# EtherTen.net
KiCad netlist of a schematic drawn in EAGLE
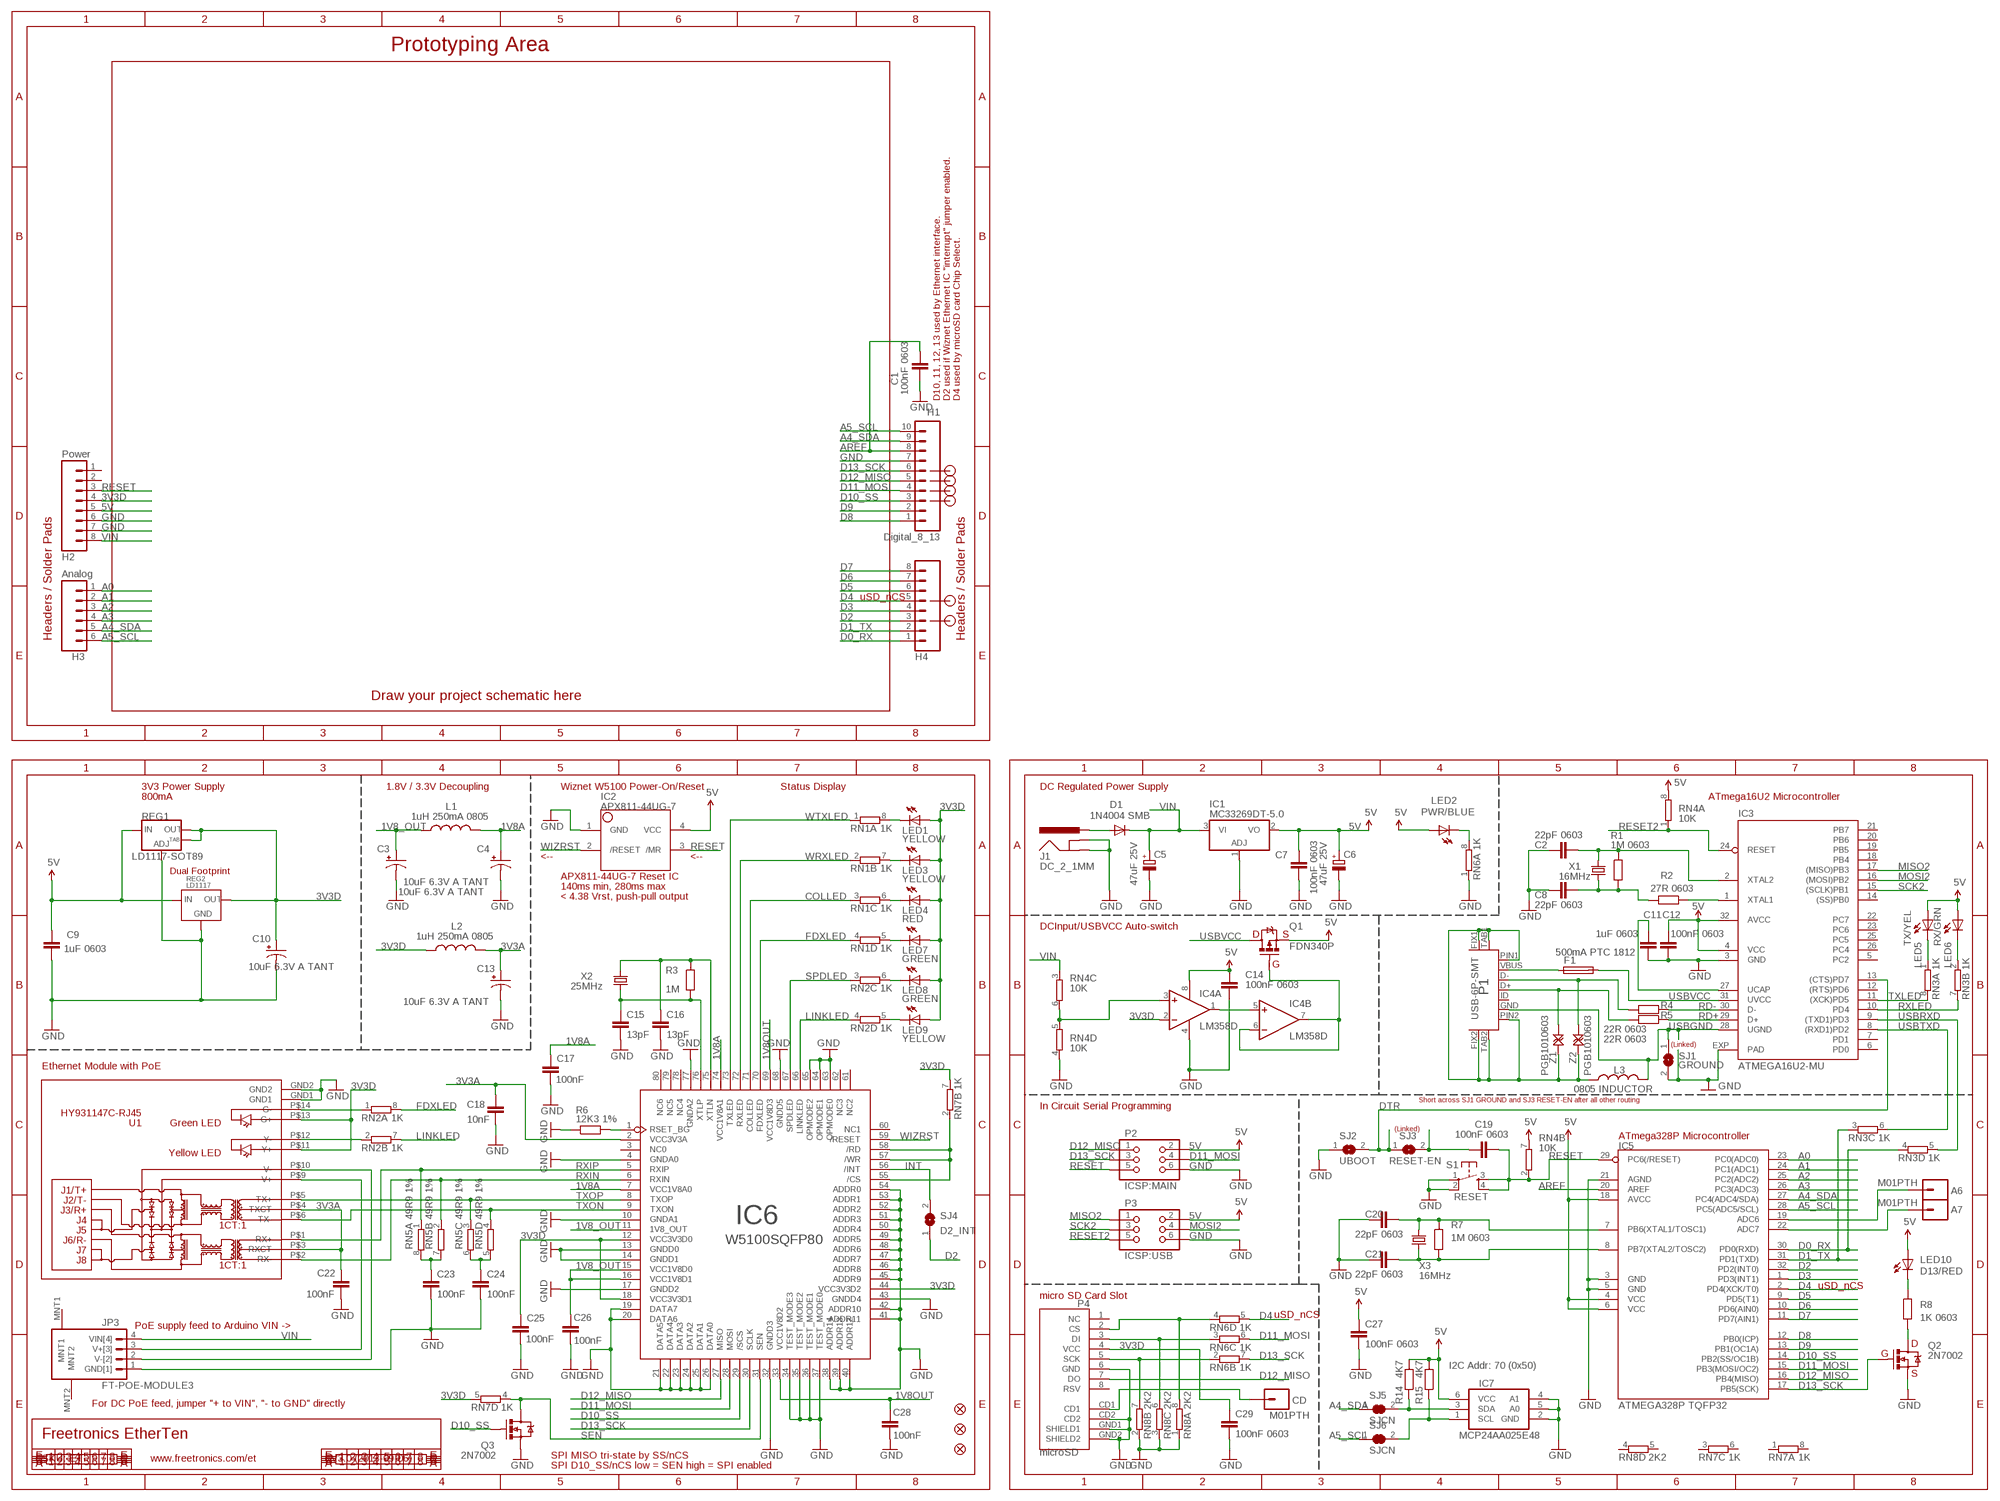
[diagram p0: schematic, sheet 1]

(export (version "E")
  (design (tool "Eeschema 10.0.6"))
  (components
    (comp (ref "A6")
      (value "M01PTH")
      (footprint "eagle-import:1X01")
      (libsource (lib "eagle-import") (part "M01PTH"))
    )
    (comp (ref "A7")
      (value "M01PTH")
      (footprint "eagle-import:1X01")
      (libsource (lib "eagle-import") (part "M01PTH"))
    )
    (comp (ref "C1")
      (value "100nF 0603")
      (footprint "eagle-import:C0603")
      (libsource (lib "eagle-import") (part "CAP0603"))
    )
    (comp (ref "C2")
      (value "22pF 0603")
      (footprint "eagle-import:C0603")
      (libsource (lib "eagle-import") (part "CAP0603"))
    )
    (comp (ref "C3")
      (value "10uF 6.3V A TANT")
      (footprint "eagle-import:EIA3216")
      (libsource (lib "eagle-import") (part "CAP_POL1206"))
    )
    (comp (ref "C4")
      (value "10uF 6.3V A TANT")
      (footprint "eagle-import:EIA3216")
      (libsource (lib "eagle-import") (part "CAP_POL1206"))
    )
    (comp (ref "C5")
      (value "47uF 25V")
      (footprint "eagle-import:PANASONIC_D")
      (libsource (lib "eagle-import") (part "CPOL-EUD"))
    )
    (comp (ref "C6")
      (value "47uF 25V")
      (footprint "eagle-import:PANASONIC_D")
      (libsource (lib "eagle-import") (part "CPOL-EUD"))
    )
    (comp (ref "C7")
      (value "100nF 0603")
      (footprint "eagle-import:C0603")
      (libsource (lib "eagle-import") (part "CAP0603"))
    )
    (comp (ref "C8")
      (value "22pF 0603")
      (footprint "eagle-import:C0603")
      (libsource (lib "eagle-import") (part "CAP0603"))
    )
    (comp (ref "C9")
      (value "1uF 0603")
      (footprint "eagle-import:C0603")
      (libsource (lib "eagle-import") (part "CAP0603"))
    )
    (comp (ref "C10")
      (value "10uF 6.3V A TANT")
      (footprint "eagle-import:EIA3216")
      (libsource (lib "eagle-import") (part "CAP_POL1206"))
    )
    (comp (ref "C11")
      (value "1uF 0603")
      (footprint "eagle-import:C0603")
      (libsource (lib "eagle-import") (part "CAP0603"))
    )
    (comp (ref "C12")
      (value "100nF 0603")
      (footprint "eagle-import:C0603")
      (libsource (lib "eagle-import") (part "CAP0603"))
    )
    (comp (ref "C13")
      (value "10uF 6.3V A TANT")
      (footprint "eagle-import:EIA3216")
      (libsource (lib "eagle-import") (part "CAP_POL1206"))
    )
    (comp (ref "C14")
      (value "100nF 0603")
      (footprint "eagle-import:C0603")
      (libsource (lib "eagle-import") (part "CAP0603"))
    )
    (comp (ref "C15")
      (value "13pF")
      (footprint "eagle-import:C0603")
      (libsource (lib "eagle-import") (part "CAP0603"))
    )
    (comp (ref "C16")
      (value "13pF")
      (footprint "eagle-import:C0603")
      (libsource (lib "eagle-import") (part "CAP0603"))
    )
    (comp (ref "C17")
      (value "100nF")
      (footprint "eagle-import:C0603")
      (libsource (lib "eagle-import") (part "CAP0603"))
    )
    (comp (ref "C18")
      (value "10nF")
      (footprint "eagle-import:C0603")
      (libsource (lib "eagle-import") (part "CAP0603"))
    )
    (comp (ref "C19")
      (value "100nF 0603")
      (footprint "eagle-import:C0603")
      (libsource (lib "eagle-import") (part "CAP0603"))
    )
    (comp (ref "C20")
      (value "22pF 0603")
      (footprint "eagle-import:C0603")
      (libsource (lib "eagle-import") (part "CAP0603"))
    )
    (comp (ref "C21")
      (value "22pF 0603")
      (footprint "eagle-import:C0603")
      (libsource (lib "eagle-import") (part "CAP0603"))
    )
    (comp (ref "C22")
      (value "100nF")
      (footprint "eagle-import:C0603")
      (libsource (lib "eagle-import") (part "CAP0603"))
    )
    (comp (ref "C23")
      (value "100nF")
      (footprint "eagle-import:C0603")
      (libsource (lib "eagle-import") (part "CAP0603"))
    )
    (comp (ref "C24")
      (value "100nF")
      (footprint "eagle-import:C0603")
      (libsource (lib "eagle-import") (part "CAP0603"))
    )
    (comp (ref "C25")
      (value "100nF")
      (footprint "eagle-import:C0603")
      (libsource (lib "eagle-import") (part "CAP0603"))
    )
    (comp (ref "C26")
      (value "100nF")
      (footprint "eagle-import:C0603")
      (libsource (lib "eagle-import") (part "CAP0603"))
    )
    (comp (ref "C27")
      (value "100nF 0603")
      (footprint "eagle-import:C0603")
      (libsource (lib "eagle-import") (part "CAP0603"))
    )
    (comp (ref "C28")
      (value "100nF")
      (footprint "eagle-import:C0603")
      (libsource (lib "eagle-import") (part "CAP0603"))
    )
    (comp (ref "C29")
      (value "100nF 0603")
      (footprint "eagle-import:C0603")
      (libsource (lib "eagle-import") (part "CAP0603"))
    )
    (comp (ref "CD")
      (value "M01PTH")
      (footprint "eagle-import:1X01")
      (libsource (lib "eagle-import") (part "M01PTH"))
    )
    (comp (ref "D1")
      (value "1N4004 SMB")
      (footprint "eagle-import:SMA-DIODE")
      (libsource (lib "eagle-import") (part "DIODESMA"))
    )
    (comp (ref "F1")
      (value "500mA PTC 1812")
      (footprint "eagle-import:1812")
      (libsource (lib "eagle-import") (part "PTC050"))
    )
    (comp (ref "FID1")
      (value "FIDUCIAL1X2.5")
      (footprint "eagle-import:FIDUCIAL-1X2.5")
      (libsource (lib "eagle-import") (part "FIDUCIAL1X2.5"))
    )
    (comp (ref "FID2")
      (value "FIDUCIAL1X2.5")
      (footprint "eagle-import:FIDUCIAL-1X2.5")
      (libsource (lib "eagle-import") (part "FIDUCIAL1X2.5"))
    )
    (comp (ref "FID3")
      (value "FIDUCIAL1X2.5")
      (footprint "eagle-import:FIDUCIAL-1X2.5")
      (libsource (lib "eagle-import") (part "FIDUCIAL1X2.5"))
    )
    (comp (ref "H1")
      (value "Digital_8_13")
      (footprint "eagle-import:1X10-S")
      (libsource (lib "eagle-import") (part "M10-SOCKET"))
    )
    (comp (ref "H2")
      (value "Power")
      (footprint "eagle-import:1X08-S")
      (libsource (lib "eagle-import") (part "M08-SOCKET"))
    )
    (comp (ref "H3")
      (value "Analog")
      (footprint "eagle-import:1X06-S")
      (libsource (lib "eagle-import") (part "M06-SOCKET"))
    )
    (comp (ref "H4")
      (value "Digital_0_7")
      (footprint "eagle-import:1X08-S")
      (libsource (lib "eagle-import") (part "M08-SOCKET"))
    )
    (comp (ref "IC1")
      (value "MC33269DT-5.0")
      (footprint "eagle-import:DPACK")
      (libsource (lib "eagle-import") (part "MC33269?D-5.0"))
    )
    (comp (ref "IC2")
      (value "APX811-44UG-7")
      (footprint "eagle-import:SOT143-R")
      (libsource (lib "eagle-import") (part "APX81X"))
    )
    (comp (ref "IC3")
      (value "ATMEGA16U2-MU")
      (footprint "eagle-import:ATMEL_QFN32")
      (libsource (lib "eagle-import") (part "ATMEGA8U2QFN"))
    )
    (comp (ref "IC4")
      (value "LM358D")
      (footprint "eagle-import:SO08")
      (libsource (lib "eagle-import") (part "LM358D"))
    )
    (comp (ref "IC5")
      (value "ATMEGA328P TQFP32")
      (footprint "eagle-import:TQFP32-08")
      (libsource (lib "eagle-import") (part "AVR-MEGA8-AI"))
    )
    (comp (ref "IC6")
      (value "W5100SQFP80")
      (footprint "eagle-import:SQFP80")
      (libsource (lib "eagle-import") (part "W5100SQFP80"))
    )
    (comp (ref "IC7")
      (value "MCP24AA025E48")
      (footprint "eagle-import:SOT23-6")
      (libsource (lib "eagle-import") (part "MCP24AA025E48"))
    )
    (comp (ref "J1")
      (value "DC_2_1MM")
      (footprint "eagle-import:POWER_JACK_SLOTS")
      (libsource (lib "eagle-import") (part "POWER_JACK-SLOTS"))
    )
    (comp (ref "JP3")
      (value "FT-POE-MODULE3")
      (footprint "eagle-import:FT-POE-MODULE-NOLABEL")
      (libsource (lib "eagle-import") (part "FT-POE-MODULE3"))
    )
    (comp (ref "L1")
      (value "1uH 250mA 0805")
      (footprint "eagle-import:L2012C")
      (libsource (lib "eagle-import") (part "L-USL2012C"))
    )
    (comp (ref "L2")
      (value "1uH 250mA 0805")
      (footprint "eagle-import:L2012C")
      (libsource (lib "eagle-import") (part "L-USL2012C"))
    )
    (comp (ref "L3")
      (value "0805 INDUCTOR")
      (footprint "eagle-import:0805-LARGE")
      (libsource (lib "eagle-import") (part "INDUCTOR0805-LARGE"))
    )
    (comp (ref "LED1")
      (value "YELLOW")
      (footprint "eagle-import:LED-0603")
      (libsource (lib "eagle-import") (part "LED0603"))
    )
    (comp (ref "LED2")
      (value "PWR/BLUE")
      (footprint "eagle-import:LED-0603")
      (libsource (lib "eagle-import") (part "LED0603"))
    )
    (comp (ref "LED3")
      (value "YELLOW")
      (footprint "eagle-import:LED-0603")
      (libsource (lib "eagle-import") (part "LED0603"))
    )
    (comp (ref "LED4")
      (value "RED")
      (footprint "eagle-import:LED-0603")
      (libsource (lib "eagle-import") (part "LED0603"))
    )
    (comp (ref "LED5")
      (value "TX/YEL")
      (footprint "eagle-import:LED-0603")
      (libsource (lib "eagle-import") (part "LED0603"))
    )
    (comp (ref "LED6")
      (value "RX/GRN")
      (footprint "eagle-import:LED-0603")
      (libsource (lib "eagle-import") (part "LED0603"))
    )
    (comp (ref "LED7")
      (value "GREEN")
      (footprint "eagle-import:LED-0603")
      (libsource (lib "eagle-import") (part "LED0603"))
    )
    (comp (ref "LED8")
      (value "GREEN")
      (footprint "eagle-import:LED-0603")
      (libsource (lib "eagle-import") (part "LED0603"))
    )
    (comp (ref "LED9")
      (value "YELLOW")
      (footprint "eagle-import:LED-0603")
      (libsource (lib "eagle-import") (part "LED0603"))
    )
    (comp (ref "LED10")
      (value "D13/RED")
      (footprint "eagle-import:LED-0603")
      (libsource (lib "eagle-import") (part "LED0603"))
    )
    (comp (ref "P1")
      (value "USB-6P-SMT")
      (footprint "eagle-import:USB-MICROB-MB05PMXX")
      (libsource (lib "eagle-import") (part "USB-6P-SMT"))
    )
    (comp (ref "P2")
      (value "ICSP:MAIN")
      (footprint "eagle-import:2X03PTH")
      (libsource (lib "eagle-import") (part "ICSPPTH"))
    )
    (comp (ref "P3")
      (value "ICSP:USB")
      (footprint "eagle-import:2X03PTH")
      (libsource (lib "eagle-import") (part "ICSPPTH"))
    )
    (comp (ref "P4")
      (value "microSD")
      (footprint "eagle-import:MICRO-SD-SOCKET-PP")
      (libsource (lib "eagle-import") (part "USD-SOCKETNEW"))
    )
    (comp (ref "Q1")
      (value "FDN340P")
      (footprint "eagle-import:SOT23")
      (libsource (lib "eagle-import") (part "MOSFET-PCHANNEL"))
    )
    (comp (ref "Q2")
      (value "2N7002")
      (footprint "eagle-import:SOT23-3")
      (libsource (lib "eagle-import") (part "MOSFET-NCHANNEL-233"))
    )
    (comp (ref "Q3")
      (value "2N7002")
      (footprint "eagle-import:SOT23-3")
      (libsource (lib "eagle-import") (part "MOSFET-NCHANNEL-233"))
    )
    (comp (ref "R1")
      (value "1M 0603")
      (footprint "eagle-import:R0603")
      (libsource (lib "eagle-import") (part "RESISTOR0603"))
    )
    (comp (ref "R2")
      (value "27R 0603")
      (footprint "eagle-import:R0603")
      (libsource (lib "eagle-import") (part "RESISTOR0603"))
    )
    (comp (ref "R3")
      (value "1M")
      (footprint "eagle-import:R0603")
      (libsource (lib "eagle-import") (part "RESISTOR0603"))
    )
    (comp (ref "R4")
      (value "22R 0603")
      (footprint "eagle-import:R0603")
      (libsource (lib "eagle-import") (part "RESISTOR0603"))
    )
    (comp (ref "R5")
      (value "22R 0603")
      (footprint "eagle-import:R0603")
      (libsource (lib "eagle-import") (part "RESISTOR0603"))
    )
    (comp (ref "R6")
      (value "12K3 1%")
      (footprint "eagle-import:R0603")
      (libsource (lib "eagle-import") (part "RESISTOR0603"))
    )
    (comp (ref "R7")
      (value "1M 0603")
      (footprint "eagle-import:R0603")
      (libsource (lib "eagle-import") (part "RESISTOR0603"))
    )
    (comp (ref "R8")
      (value "1K 0603")
      (footprint "eagle-import:R0603")
      (libsource (lib "eagle-import") (part "RESISTOR0603"))
    )
    (comp (ref "R14")
      (value "4K7")
      (footprint "eagle-import:R0603")
      (libsource (lib "eagle-import") (part "RESISTOR0603"))
    )
    (comp (ref "R15")
      (value "4K7")
      (footprint "eagle-import:R0603")
      (libsource (lib "eagle-import") (part "RESISTOR0603"))
    )
    (comp (ref "REG1")
      (value "LD1117-SOT89")
      (footprint "eagle-import:SOT89")
      (libsource (lib "eagle-import") (part "V_REG_LM1117SOT89"))
    )
    (comp (ref "REG2")
      (value "LD1117")
      (footprint "eagle-import:SOT-223")
      (libsource (lib "eagle-import") (part "LD1117"))
    )
    (comp (ref "RN1")
      (value "1K")
      (footprint "eagle-import:CAY16")
      (libsource (lib "eagle-import") (part "4R-NCAY16"))
    )
    (comp (ref "RN2")
      (value "1K")
      (footprint "eagle-import:CAY16")
      (libsource (lib "eagle-import") (part "4R-NCAY16"))
    )
    (comp (ref "RN3")
      (value "1K")
      (footprint "eagle-import:CAY16")
      (libsource (lib "eagle-import") (part "4R-NCAY16"))
    )
    (comp (ref "RN4")
      (value "10K")
      (footprint "eagle-import:CAY16")
      (libsource (lib "eagle-import") (part "4R-NCAY16"))
    )
    (comp (ref "RN5")
      (value "49R9 1%")
      (footprint "eagle-import:CAY16")
      (libsource (lib "eagle-import") (part "4R-NCAY16"))
    )
    (comp (ref "RN6")
      (value "1K")
      (footprint "eagle-import:CAY16")
      (libsource (lib "eagle-import") (part "4R-NCAY16"))
    )
    (comp (ref "RN7")
      (value "1K")
      (footprint "eagle-import:CAY16")
      (libsource (lib "eagle-import") (part "4R-NCAY16"))
    )
    (comp (ref "RN8")
      (value "2K2")
      (footprint "eagle-import:CAY16")
      (libsource (lib "eagle-import") (part "4R-NCAY16"))
    )
    (comp (ref "S1")
      (value "RESET")
      (footprint "eagle-import:TACTILE_SMD-6MM")
      (libsource (lib "eagle-import") (part "TAC_SWITCH-SMT-6"))
    )
    (comp (ref "SJ1")
      (value "GROUND")
      (footprint "eagle-import:SJ")
      (libsource (lib "eagle-import") (part "SJ"))
    )
    (comp (ref "SJ2")
      (value "UBOOT")
      (footprint "eagle-import:SJ")
      (libsource (lib "eagle-import") (part "SJ"))
    )
    (comp (ref "SJ3")
      (value "RESET-EN")
      (footprint "eagle-import:SJ")
      (libsource (lib "eagle-import") (part "SJ"))
    )
    (comp (ref "SJ4")
      (value "D2_INT")
      (footprint "eagle-import:SJ")
      (libsource (lib "eagle-import") (part "SJ"))
    )
    (comp (ref "SJ5")
      (value "SJCN")
      (footprint "eagle-import:SJC")
      (libsource (lib "eagle-import") (part "SJCN"))
    )
    (comp (ref "SJ6")
      (value "SJCN")
      (footprint "eagle-import:SJC")
      (libsource (lib "eagle-import") (part "SJCN"))
    )
    (comp (ref "U1")
      (value "HY931147C-RJ45")
      (footprint "eagle-import:HY931147C")
      (libsource (lib "eagle-import") (part "HY931147C-RJ45"))
    )
    (comp (ref "X1")
      (value "16MHz")
      (footprint "eagle-import:HC49U-V")
      (libsource (lib "eagle-import") (part "CRYSTALHC49UV"))
    )
    (comp (ref "X2")
      (value "25MHz")
      (footprint "eagle-import:HC49U-V")
      (libsource (lib "eagle-import") (part "CRYSTALHC49UV"))
    )
    (comp (ref "X3")
      (value "16MHz")
      (footprint "eagle-import:HC49U-V")
      (libsource (lib "eagle-import") (part "CRYSTALHC49UV"))
    )
    (comp (ref "Z1")
      (value "PGB1010603")
      (footprint "eagle-import:TVS0603")
      (libsource (lib "eagle-import") (part "TVS0603"))
    )
    (comp (ref "Z2")
      (value "PGB1010603")
      (footprint "eagle-import:TVS0603")
      (libsource (lib "eagle-import") (part "TVS0603"))
    )
  )
  (nets
    (net (code "1") (name "/1V8A") (class "Default")
      (node (ref "C17") (pin "1") (pinfunction "1_1") (pintype "passive"))
      (node (ref "C4") (pin "A") (pinfunction "+_A") (pintype "passive"))
      (node (ref "IC6") (pin "7") (pinfunction "VCC1V8A0_7") (pintype "bidirectional"))
      (node (ref "IC6") (pin "74") (pinfunction "VCC1V8A1_74") (pintype "bidirectional"))
      (node (ref "L1") (pin "2") (pinfunction "2_2") (pintype "passive"))
    )
    (net (code "2") (name "/1V8OUT") (class "Default")
      (node (ref "C28") (pin "1") (pinfunction "1_1") (pintype "passive"))
      (node (ref "IC6") (pin "33") (pinfunction "VCC1V8D2_33") (pintype "bidirectional"))
      (node (ref "IC6") (pin "69") (pinfunction "VCC1V8D3_69") (pintype "bidirectional"))
    )
    (net (code "3") (name "/1V8_OUT") (class "Default")
      (node (ref "C26") (pin "1") (pinfunction "1_1") (pintype "passive"))
      (node (ref "C3") (pin "A") (pinfunction "+_A") (pintype "passive"))
      (node (ref "IC6") (pin "11") (pinfunction "1V8_OUT_11") (pintype "bidirectional"))
      (node (ref "IC6") (pin "15") (pinfunction "VCC1V8D0_15") (pintype "bidirectional"))
      (node (ref "IC6") (pin "16") (pinfunction "VCC1V8D1_16") (pintype "bidirectional"))
      (node (ref "L1") (pin "1") (pinfunction "1_1") (pintype "passive"))
    )
    (net (code "4") (name "/3V3A") (class "Default")
      (node (ref "C13") (pin "A") (pinfunction "+_A") (pintype "passive"))
      (node (ref "C18") (pin "1") (pinfunction "1_1") (pintype "passive"))
      (node (ref "C22") (pin "1") (pinfunction "1_1") (pintype "passive"))
      (node (ref "IC6") (pin "2") (pinfunction "VCC3V3A_2") (pintype "bidirectional"))
      (node (ref "L2") (pin "2") (pinfunction "2_2") (pintype "passive"))
      (node (ref "U1") (pin "P$3") (pinfunction "RXCT_P$3") (pintype "bidirectional"))
      (node (ref "U1") (pin "P$4") (pinfunction "TXCT_P$4") (pintype "bidirectional"))
    )
    (net (code "5") (name "/3V3D") (class "Default")
      (node (ref "C10") (pin "A") (pinfunction "+_A") (pintype "passive"))
      (node (ref "C25") (pin "1") (pinfunction "1_1") (pintype "passive"))
      (node (ref "C29") (pin "1") (pinfunction "1_1") (pintype "passive"))
      (node (ref "H2") (pin "4") (pinfunction "4_4") (pintype "passive"))
      (node (ref "IC4") (pin "2") (pinfunction "-IN_2") (pintype "input"))
      (node (ref "IC6") (pin "12") (pinfunction "VCC3V3D0_12") (pintype "bidirectional"))
      (node (ref "IC6") (pin "18") (pinfunction "VCC3V3D1_18") (pintype "bidirectional"))
      (node (ref "IC6") (pin "44") (pinfunction "VCC3V3D2_44") (pintype "bidirectional"))
      (node (ref "L2") (pin "1") (pinfunction "1_1") (pintype "passive"))
      (node (ref "LED1") (pin "A") (pinfunction "A_A") (pintype "passive"))
      (node (ref "LED3") (pin "A") (pinfunction "A_A") (pintype "passive"))
      (node (ref "LED4") (pin "A") (pinfunction "A_A") (pintype "passive"))
      (node (ref "LED7") (pin "A") (pinfunction "A_A") (pintype "passive"))
      (node (ref "LED8") (pin "A") (pinfunction "A_A") (pintype "passive"))
      (node (ref "LED9") (pin "A") (pinfunction "A_A") (pintype "passive"))
      (node (ref "P4") (pin "4") (pinfunction "VCC_4") (pintype "bidirectional"))
      (node (ref "REG1") (pin "2") (pinfunction "OUT_2") (pintype "output"))
      (node (ref "REG1") (pin "4") (pinfunction "OUT_4") (pintype "output"))
      (node (ref "REG2") (pin "2") (pinfunction "OUT_2") (pintype "power_in"))
      (node (ref "REG2") (pin "4") (pinfunction "OUT_4") (pintype "power_in"))
      (node (ref "RN7") (pin "5") (pinfunction "2_5") (pintype "passive"))
      (node (ref "RN7") (pin "7") (pinfunction "2_7") (pintype "passive"))
      (node (ref "U1") (pin "P$11") (pinfunction "Y+_P$11") (pintype "bidirectional"))
      (node (ref "U1") (pin "P$13") (pinfunction "G+_P$13") (pintype "bidirectional"))
    )
    (net (code "6") (name "/A0") (class "Default")
      (node (ref "H3") (pin "1") (pinfunction "1_1") (pintype "passive"))
      (node (ref "IC5") (pin "23") (pinfunction "PC0(ADC0)_23") (pintype "bidirectional"))
    )
    (net (code "7") (name "/A1") (class "Default")
      (node (ref "H3") (pin "2") (pinfunction "2_2") (pintype "passive"))
      (node (ref "IC5") (pin "24") (pinfunction "PC1(ADC1)_24") (pintype "bidirectional"))
    )
    (net (code "8") (name "/A2") (class "Default")
      (node (ref "H3") (pin "3") (pinfunction "3_3") (pintype "passive"))
      (node (ref "IC5") (pin "25") (pinfunction "PC2(ADC2)_25") (pintype "bidirectional"))
    )
    (net (code "9") (name "/A3") (class "Default")
      (node (ref "H3") (pin "4") (pinfunction "4_4") (pintype "passive"))
      (node (ref "IC5") (pin "26") (pinfunction "PC3(ADC3)_26") (pintype "bidirectional"))
    )
    (net (code "10") (name "/A4_SDA") (class "Default")
      (node (ref "H1") (pin "9") (pinfunction "9_9") (pintype "passive"))
      (node (ref "H3") (pin "5") (pinfunction "5_5") (pintype "passive"))
      (node (ref "IC5") (pin "27") (pinfunction "PC4(ADC4/SDA)_27") (pintype "bidirectional"))
      (node (ref "SJ5") (pin "1") (pinfunction "1_1") (pintype "passive"))
    )
    (net (code "11") (name "/A5_SCL") (class "Default")
      (node (ref "H1") (pin "10") (pinfunction "10_10") (pintype "passive"))
      (node (ref "H3") (pin "6") (pinfunction "6_6") (pintype "passive"))
      (node (ref "IC5") (pin "28") (pinfunction "PC5(ADC5/SCL)_28") (pintype "bidirectional"))
      (node (ref "SJ6") (pin "1") (pinfunction "1_1") (pintype "passive"))
    )
    (net (code "12") (name "/AREF") (class "Default")
      (node (ref "C1") (pin "1") (pinfunction "1_1") (pintype "passive"))
      (node (ref "H1") (pin "8") (pinfunction "8_8") (pintype "passive"))
      (node (ref "IC5") (pin "20") (pinfunction "AREF_20") (pintype "bidirectional"))
    )
    (net (code "13") (name "/COLLED") (class "Default")
      (node (ref "IC6") (pin "71") (pinfunction "COLLED_71") (pintype "bidirectional"))
      (node (ref "RN1") (pin "3") (pinfunction "1_3") (pintype "passive"))
    )
    (net (code "14") (name "/D0_RX") (class "Default")
      (node (ref "H4") (pin "1") (pinfunction "1_1") (pintype "passive"))
      (node (ref "IC5") (pin "30") (pinfunction "PD0(RXD)_30") (pintype "bidirectional"))
      (node (ref "RN3") (pin "4") (pinfunction "1_4") (pintype "passive"))
    )
    (net (code "15") (name "/D1_TX") (class "Default")
      (node (ref "H4") (pin "2") (pinfunction "2_2") (pintype "passive"))
      (node (ref "IC5") (pin "31") (pinfunction "PD1(TXD)_31") (pintype "bidirectional"))
      (node (ref "RN3") (pin "3") (pinfunction "1_3") (pintype "passive"))
    )
    (net (code "16") (name "/D2") (class "Default")
      (node (ref "H4") (pin "3") (pinfunction "3_3") (pintype "passive"))
      (node (ref "IC5") (pin "32") (pinfunction "PD2(INT0)_32") (pintype "bidirectional"))
      (node (ref "SJ4") (pin "1") (pinfunction "1_1") (pintype "passive"))
    )
    (net (code "17") (name "/D3") (class "Default")
      (node (ref "H4") (pin "4") (pinfunction "4_4") (pintype "passive"))
      (node (ref "IC5") (pin "1") (pinfunction "PD3(INT1)_1") (pintype "bidirectional"))
    )
    (net (code "18") (name "/D4") (class "Default")
      (node (ref "H4") (pin "5") (pinfunction "5_5") (pintype "passive"))
      (node (ref "IC5") (pin "2") (pinfunction "PD4(XCK/T0)_2") (pintype "bidirectional"))
      (node (ref "RN6") (pin "5") (pinfunction "2_5") (pintype "passive"))
    )
    (net (code "19") (name "/D5") (class "Default")
      (node (ref "H4") (pin "6") (pinfunction "6_6") (pintype "passive"))
      (node (ref "IC5") (pin "9") (pinfunction "PD5(T1)_9") (pintype "bidirectional"))
    )
    (net (code "20") (name "/D6") (class "Default")
      (node (ref "H4") (pin "7") (pinfunction "7_7") (pintype "passive"))
      (node (ref "IC5") (pin "10") (pinfunction "PD6(AIN0)_10") (pintype "bidirectional"))
    )
    (net (code "21") (name "/D7") (class "Default")
      (node (ref "H4") (pin "8") (pinfunction "8_8") (pintype "passive"))
      (node (ref "IC5") (pin "11") (pinfunction "PD7(AIN1)_11") (pintype "bidirectional"))
    )
    (net (code "22") (name "/D8") (class "Default")
      (node (ref "H1") (pin "1") (pinfunction "1_1") (pintype "passive"))
      (node (ref "IC5") (pin "12") (pinfunction "PB0(ICP)_12") (pintype "bidirectional"))
    )
    (net (code "23") (name "/D9") (class "Default")
      (node (ref "H1") (pin "2") (pinfunction "2_2") (pintype "passive"))
      (node (ref "IC5") (pin "13") (pinfunction "PB1(OC1A)_13") (pintype "bidirectional"))
    )
    (net (code "24") (name "/D10_SS") (class "Default")
      (node (ref "H1") (pin "3") (pinfunction "3_3") (pintype "passive"))
      (node (ref "IC5") (pin "14") (pinfunction "PB2(SS/OC1B)_14") (pintype "bidirectional"))
      (node (ref "IC6") (pin "29") (pinfunction "/SCS_29") (pintype "bidirectional"))
      (node (ref "Q3") (pin "1") (pinfunction "G_1") (pintype "passive"))
    )
    (net (code "25") (name "/D11_MOSI") (class "Default")
      (node (ref "H1") (pin "4") (pinfunction "4_4") (pintype "passive"))
      (node (ref "IC5") (pin "15") (pinfunction "PB3(MOSI/OC2)_15") (pintype "bidirectional"))
      (node (ref "IC6") (pin "28") (pinfunction "MOSI_28") (pintype "bidirectional"))
      (node (ref "P2") (pin "4") (pinfunction "4_4") (pintype "passive"))
      (node (ref "RN6") (pin "6") (pinfunction "2_6") (pintype "passive"))
    )
    (net (code "26") (name "/D12_MISO") (class "Default")
      (node (ref "H1") (pin "5") (pinfunction "5_5") (pintype "passive"))
      (node (ref "IC5") (pin "16") (pinfunction "PB4(MISO)_16") (pintype "bidirectional"))
      (node (ref "IC6") (pin "27") (pinfunction "MISO_27") (pintype "bidirectional"))
      (node (ref "P2") (pin "1") (pinfunction "1_1") (pintype "passive"))
      (node (ref "P4") (pin "7") (pinfunction "DO_7") (pintype "bidirectional"))
    )
    (net (code "27") (name "/D13_SCK") (class "Default")
      (node (ref "H1") (pin "6") (pinfunction "6_6") (pintype "passive"))
      (node (ref "IC5") (pin "17") (pinfunction "PB5(SCK)_17") (pintype "bidirectional"))
      (node (ref "IC6") (pin "30") (pinfunction "SCLK_30") (pintype "bidirectional"))
      (node (ref "P2") (pin "3") (pinfunction "3_3") (pintype "passive"))
      (node (ref "Q2") (pin "1") (pinfunction "G_1") (pintype "passive"))
      (node (ref "RN6") (pin "7") (pinfunction "2_7") (pintype "passive"))
    )
    (net (code "28") (name "/DTR") (class "Default")
      (node (ref "IC3") (pin "13") (pinfunction "(CTS)PD7_13") (pintype "bidirectional"))
      (node (ref "SJ2") (pin "2") (pinfunction "2_2") (pintype "passive"))
      (node (ref "SJ3") (pin "1") (pinfunction "1_1") (pintype "passive"))
    )
    (net (code "29") (name "/FDXLED") (class "Default")
      (node (ref "IC6") (pin "70") (pinfunction "FDXLED_70") (pintype "bidirectional"))
      (node (ref "RN1") (pin "4") (pinfunction "1_4") (pintype "passive"))
      (node (ref "RN2") (pin "8") (pinfunction "2_8") (pintype "passive"))
    )
    (net (code "30") (name "/INT") (class "Default")
      (node (ref "IC6") (pin "56") (pinfunction "/INT_56") (pintype "bidirectional"))
      (node (ref "SJ4") (pin "2") (pinfunction "2_2") (pintype "passive"))
    )
    (net (code "31") (name "/LINKLED") (class "Default")
      (node (ref "IC6") (pin "66") (pinfunction "LINKLED_66") (pintype "bidirectional"))
      (node (ref "RN2") (pin "4") (pinfunction "1_4") (pintype "passive"))
      (node (ref "RN2") (pin "7") (pinfunction "2_7") (pintype "passive"))
    )
    (net (code "32") (name "/MISO2") (class "Default")
      (node (ref "IC3") (pin "17") (pinfunction "(MISO)PB3_17") (pintype "bidirectional"))
      (node (ref "P3") (pin "1") (pinfunction "1_1") (pintype "passive"))
    )
    (net (code "33") (name "/MOSI2") (class "Default")
      (node (ref "IC3") (pin "16") (pinfunction "(MOSI)PB2_16") (pintype "bidirectional"))
      (node (ref "P3") (pin "4") (pinfunction "4_4") (pintype "passive"))
    )
    (net (code "34") (name "/RD+") (class "Default")
      (node (ref "IC3") (pin "29") (pinfunction "D+_29") (pintype "bidirectional"))
      (node (ref "R5") (pin "1") (pinfunction "1_1") (pintype "passive"))
    )
    (net (code "35") (name "/RD-") (class "Default")
      (node (ref "IC3") (pin "30") (pinfunction "D-_30") (pintype "bidirectional"))
      (node (ref "R4") (pin "1") (pinfunction "1_1") (pintype "passive"))
    )
    (net (code "36") (name "/RESET") (class "Default")
      (node (ref "C19") (pin "2") (pinfunction "2_2") (pintype "passive"))
      (node (ref "H2") (pin "3") (pinfunction "3_3") (pintype "passive"))
      (node (ref "IC2") (pin "3") (pinfunction "/MR_3") (pintype "input"))
      (node (ref "IC5") (pin "29") (pinfunction "PC6(/RESET)_29") (pintype "bidirectional"))
      (node (ref "P2") (pin "5") (pinfunction "5_5") (pintype "passive"))
      (node (ref "RN4") (pin "2") (pinfunction "1_2") (pintype "passive"))
      (node (ref "S1") (pin "3") (pinfunction "3_3") (pintype "passive"))
      (node (ref "S1") (pin "4") (pinfunction "4_4") (pintype "passive"))
    )
    (net (code "37") (name "/RESET2") (class "Default")
      (node (ref "IC3") (pin "24") (pinfunction "RESET_24") (pintype "input"))
      (node (ref "P3") (pin "5") (pinfunction "5_5") (pintype "passive"))
      (node (ref "RN4") (pin "1") (pinfunction "1_1") (pintype "passive"))
    )
    (net (code "38") (name "/RXIN") (class "Default")
      (node (ref "IC6") (pin "6") (pinfunction "RXIN_6") (pintype "bidirectional"))
      (node (ref "RN5") (pin "2") (pinfunction "1_2") (pintype "passive"))
      (node (ref "U1") (pin "P$2") (pinfunction "RX-_P$2") (pintype "bidirectional"))
    )
    (net (code "39") (name "/RXIP") (class "Default")
      (node (ref "IC6") (pin "5") (pinfunction "RXIP_5") (pintype "bidirectional"))
      (node (ref "RN5") (pin "1") (pinfunction "1_1") (pintype "passive"))
      (node (ref "U1") (pin "P$1") (pinfunction "RX+_P$1") (pintype "bidirectional"))
    )
    (net (code "40") (name "/RXLED") (class "Default")
      (node (ref "IC3") (pin "10") (pinfunction "PD4_10") (pintype "bidirectional"))
      (node (ref "RN3") (pin "7") (pinfunction "2_7") (pintype "passive"))
    )
    (net (code "41") (name "/SCK2") (class "Default")
      (node (ref "IC3") (pin "15") (pinfunction "(SCLK)PB1_15") (pintype "bidirectional"))
      (node (ref "P3") (pin "3") (pinfunction "3_3") (pintype "passive"))
    )
    (net (code "42") (name "/SEN") (class "Default")
      (node (ref "IC6") (pin "31") (pinfunction "SEN_31") (pintype "bidirectional"))
      (node (ref "Q3") (pin "3") (pinfunction "D_3") (pintype "passive"))
      (node (ref "RN7") (pin "4") (pinfunction "1_4") (pintype "passive"))
    )
    (net (code "43") (name "/SPDLED") (class "Default")
      (node (ref "IC6") (pin "67") (pinfunction "SPDLED_67") (pintype "bidirectional"))
      (node (ref "RN2") (pin "3") (pinfunction "1_3") (pintype "passive"))
    )
    (net (code "44") (name "/TXLED") (class "Default")
      (node (ref "IC3") (pin "11") (pinfunction "(XCK)PD5_11") (pintype "bidirectional"))
      (node (ref "RN3") (pin "8") (pinfunction "2_8") (pintype "passive"))
    )
    (net (code "45") (name "/TXON") (class "Default")
      (node (ref "IC6") (pin "9") (pinfunction "TXON_9") (pintype "bidirectional"))
      (node (ref "RN5") (pin "4") (pinfunction "1_4") (pintype "passive"))
      (node (ref "U1") (pin "P$6") (pinfunction "TX-_P$6") (pintype "bidirectional"))
    )
    (net (code "46") (name "/TXOP") (class "Default")
      (node (ref "IC6") (pin "8") (pinfunction "TXOP_8") (pintype "bidirectional"))
      (node (ref "RN5") (pin "3") (pinfunction "1_3") (pintype "passive"))
      (node (ref "U1") (pin "P$5") (pinfunction "TX+_P$5") (pintype "bidirectional"))
    )
    (net (code "47") (name "/USBGND") (class "Default")
      (node (ref "IC3") (pin "28") (pinfunction "UGND_28") (pintype "power_in"))
      (node (ref "L3") (pin "2") (pinfunction "2_2") (pintype "passive"))
      (node (ref "P1") (pin "GND") (pinfunction "GND_GND") (pintype "bidirectional"))
      (node (ref "SJ1") (pin "1") (pinfunction "1_1") (pintype "passive"))
    )
    (net (code "48") (name "/USBRXD") (class "Default")
      (node (ref "IC3") (pin "9") (pinfunction "(TXD1)PD3_9") (pintype "bidirectional"))
      (node (ref "RN3") (pin "5") (pinfunction "2_5") (pintype "passive"))
    )
    (net (code "49") (name "/USBTXD") (class "Default")
      (node (ref "IC3") (pin "8") (pinfunction "(RXD1)PD2_8") (pintype "bidirectional"))
      (node (ref "RN3") (pin "6") (pinfunction "2_6") (pintype "passive"))
    )
    (net (code "50") (name "/USBVCC") (class "Default")
      (node (ref "F1") (pin "2") (pinfunction "2_2") (pintype "passive"))
      (node (ref "IC3") (pin "31") (pinfunction "UVCC_31") (pintype "power_in"))
      (node (ref "Q1") (pin "3") (pinfunction "D_3") (pintype "passive"))
    )
    (net (code "51") (name "/VIN") (class "Default")
      (node (ref "C5") (pin "+") (pinfunction "+_+") (pintype "passive"))
      (node (ref "D1") (pin "C") (pinfunction "C_C") (pintype "passive"))
      (node (ref "H2") (pin "8") (pinfunction "8_8") (pintype "passive"))
      (node (ref "IC1") (pin "3") (pinfunction "VI_3") (pintype "input"))
      (node (ref "JP3") (pin "4") (pinfunction "VIN[4]_4") (pintype "passive"))
      (node (ref "RN4") (pin "3") (pinfunction "1_3") (pintype "passive"))
    )
    (net (code "52") (name "/WIZRST") (class "Default")
      (node (ref "IC2") (pin "2") (pinfunction "/RESET_2") (pintype "output"))
      (node (ref "IC6") (pin "59") (pinfunction "/RESET_59") (pintype "bidirectional"))
    )
    (net (code "53") (name "/WRXLED") (class "Default")
      (node (ref "IC6") (pin "72") (pinfunction "RXLED_72") (pintype "bidirectional"))
      (node (ref "RN1") (pin "2") (pinfunction "1_2") (pintype "passive"))
    )
    (net (code "54") (name "/WTXLED") (class "Default")
      (node (ref "IC6") (pin "73") (pinfunction "TXLED_73") (pintype "bidirectional"))
      (node (ref "RN1") (pin "1") (pinfunction "1_1") (pintype "passive"))
    )
    (net (code "55") (name "5V") (class "Default")
      (node (ref "C12") (pin "1") (pinfunction "1_1") (pintype "passive"))
      (node (ref "C14") (pin "1") (pinfunction "1_1") (pintype "passive"))
      (node (ref "C27") (pin "1") (pinfunction "1_1") (pintype "passive"))
      (node (ref "C6") (pin "+") (pinfunction "+_+") (pintype "passive"))
      (node (ref "C7") (pin "1") (pinfunction "1_1") (pintype "passive"))
      (node (ref "C9") (pin "1") (pinfunction "1_1") (pintype "passive"))
      (node (ref "H2") (pin "5") (pinfunction "5_5") (pintype "passive"))
      (node (ref "IC1") (pin "2") (pinfunction "VO_2") (pintype "passive"))
      (node (ref "IC2") (pin "4") (pinfunction "VCC_4") (pintype "power_in"))
      (node (ref "IC3") (pin "32") (pinfunction "AVCC_32") (pintype "power_in"))
      (node (ref "IC3") (pin "4") (pinfunction "VCC_4") (pintype "power_in"))
      (node (ref "IC4") (pin "8") (pinfunction "V+_8") (pintype "power_in"))
      (node (ref "IC5") (pin "18") (pinfunction "AVCC_18") (pintype "bidirectional"))
      (node (ref "IC5") (pin "4") (pinfunction "VCC_4") (pintype "bidirectional"))
      (node (ref "IC5") (pin "6") (pinfunction "VCC_6") (pintype "bidirectional"))
      (node (ref "IC7") (pin "6") (pinfunction "VCC_6") (pintype "power_in"))
      (node (ref "LED10") (pin "A") (pinfunction "A_A") (pintype "passive"))
      (node (ref "LED2") (pin "A") (pinfunction "A_A") (pintype "passive"))
      (node (ref "LED5") (pin "A") (pinfunction "A_A") (pintype "passive"))
      (node (ref "LED6") (pin "A") (pinfunction "A_A") (pintype "passive"))
      (node (ref "P2") (pin "2") (pinfunction "2_2") (pintype "passive"))
      (node (ref "P3") (pin "2") (pinfunction "2_2") (pintype "passive"))
      (node (ref "Q1") (pin "2") (pinfunction "S_2") (pintype "passive"))
      (node (ref "R14") (pin "1") (pinfunction "1_1") (pintype "passive"))
      (node (ref "R15") (pin "1") (pinfunction "1_1") (pintype "passive"))
      (node (ref "REG1") (pin "3") (pinfunction "IN_3") (pintype "input"))
      (node (ref "REG2") (pin "3") (pinfunction "IN_3") (pintype "input"))
      (node (ref "RN4") (pin "7") (pinfunction "2_7") (pintype "passive"))
      (node (ref "RN4") (pin "8") (pinfunction "2_8") (pintype "passive"))
    )
    (net (code "56") (name "GND") (class "Default")
      (node (ref "C1") (pin "2") (pinfunction "2_2") (pintype "passive"))
      (node (ref "C10") (pin "C") (pinfunction "-_C") (pintype "passive"))
      (node (ref "C11") (pin "2") (pinfunction "2_2") (pintype "passive"))
      (node (ref "C12") (pin "2") (pinfunction "2_2") (pintype "passive"))
      (node (ref "C13") (pin "C") (pinfunction "-_C") (pintype "passive"))
      (node (ref "C14") (pin "2") (pinfunction "2_2") (pintype "passive"))
      (node (ref "C15") (pin "2") (pinfunction "2_2") (pintype "passive"))
      (node (ref "C16") (pin "2") (pinfunction "2_2") (pintype "passive"))
      (node (ref "C17") (pin "2") (pinfunction "2_2") (pintype "passive"))
      (node (ref "C18") (pin "2") (pinfunction "2_2") (pintype "passive"))
      (node (ref "C2") (pin "1") (pinfunction "1_1") (pintype "passive"))
      (node (ref "C20") (pin "1") (pinfunction "1_1") (pintype "passive"))
      (node (ref "C21") (pin "1") (pinfunction "1_1") (pintype "passive"))
      (node (ref "C22") (pin "2") (pinfunction "2_2") (pintype "passive"))
      (node (ref "C23") (pin "2") (pinfunction "2_2") (pintype "passive"))
      (node (ref "C24") (pin "2") (pinfunction "2_2") (pintype "passive"))
      (node (ref "C25") (pin "2") (pinfunction "2_2") (pintype "passive"))
      (node (ref "C26") (pin "2") (pinfunction "2_2") (pintype "passive"))
      (node (ref "C27") (pin "2") (pinfunction "2_2") (pintype "passive"))
      (node (ref "C28") (pin "2") (pinfunction "2_2") (pintype "passive"))
      (node (ref "C29") (pin "2") (pinfunction "2_2") (pintype "passive"))
      (node (ref "C3") (pin "C") (pinfunction "-_C") (pintype "passive"))
      (node (ref "C4") (pin "C") (pinfunction "-_C") (pintype "passive"))
      (node (ref "C5") (pin "-") (pinfunction "-_-") (pintype "passive"))
      (node (ref "C6") (pin "-") (pinfunction "-_-") (pintype "passive"))
      (node (ref "C7") (pin "2") (pinfunction "2_2") (pintype "passive"))
      (node (ref "C8") (pin "1") (pinfunction "1_1") (pintype "passive"))
      (node (ref "C9") (pin "2") (pinfunction "2_2") (pintype "passive"))
      (node (ref "H1") (pin "7") (pinfunction "7_7") (pintype "passive"))
      (node (ref "H2") (pin "6") (pinfunction "6_6") (pintype "passive"))
      (node (ref "H2") (pin "7") (pinfunction "7_7") (pintype "passive"))
      (node (ref "IC1") (pin "1") (pinfunction "ADJ_1") (pintype "input"))
      (node (ref "IC2") (pin "1") (pinfunction "GND_1") (pintype "power_in"))
      (node (ref "IC3") (pin "3") (pinfunction "GND_3") (pintype "power_in"))
      (node (ref "IC3") (pin "EXP") (pinfunction "PAD_EXP") (pintype "power_in"))
      (node (ref "IC4") (pin "4") (pinfunction "V-_4") (pintype "power_in"))
      (node (ref "IC5") (pin "21") (pinfunction "AGND_21") (pintype "bidirectional"))
      (node (ref "IC5") (pin "3") (pinfunction "GND_3") (pintype "bidirectional"))
      (node (ref "IC5") (pin "5") (pinfunction "GND_5") (pintype "bidirectional"))
      (node (ref "IC6") (pin "10") (pinfunction "GNDA1_10") (pintype "bidirectional"))
      (node (ref "IC6") (pin "13") (pinfunction "GNDD0_13") (pintype "bidirectional"))
      (node (ref "IC6") (pin "14") (pinfunction "GNDD1_14") (pintype "bidirectional"))
      (node (ref "IC6") (pin "17") (pinfunction "GNDD2_17") (pintype "bidirectional"))
      (node (ref "IC6") (pin "19") (pinfunction "DATA7_19") (pintype "bidirectional"))
      (node (ref "IC6") (pin "20") (pinfunction "DATA6_20") (pintype "bidirectional"))
      (node (ref "IC6") (pin "21") (pinfunction "DATA5_21") (pintype "bidirectional"))
      (node (ref "IC6") (pin "22") (pinfunction "DATA4_22") (pintype "bidirectional"))
      (node (ref "IC6") (pin "23") (pinfunction "DATA3_23") (pintype "bidirectional"))
      (node (ref "IC6") (pin "24") (pinfunction "DATA2_24") (pintype "bidirectional"))
      (node (ref "IC6") (pin "25") (pinfunction "DATA1_25") (pintype "bidirectional"))
      (node (ref "IC6") (pin "26") (pinfunction "DATA0_26") (pintype "bidirectional"))
      (node (ref "IC6") (pin "32") (pinfunction "GNDD3_32") (pintype "bidirectional"))
      (node (ref "IC6") (pin "34") (pinfunction "TEST_MODE3_34") (pintype "bidirectional"))
      (node (ref "IC6") (pin "35") (pinfunction "TEST_MODE2_35") (pintype "bidirectional"))
      (node (ref "IC6") (pin "36") (pinfunction "TEST_MODE1_36") (pintype "bidirectional"))
      (node (ref "IC6") (pin "37") (pinfunction "TEST_MODE0_37") (pintype "bidirectional"))
      (node (ref "IC6") (pin "38") (pinfunction "ADDR14_38") (pintype "bidirectional"))
      (node (ref "IC6") (pin "39") (pinfunction "ADDR13_39") (pintype "bidirectional"))
      (node (ref "IC6") (pin "4") (pinfunction "GNDA0_4") (pintype "bidirectional"))
      (node (ref "IC6") (pin "40") (pinfunction "ADDR12_40") (pintype "bidirectional"))
      (node (ref "IC6") (pin "41") (pinfunction "ADDR11_41") (pintype "bidirectional"))
      (node (ref "IC6") (pin "42") (pinfunction "ADDR10_42") (pintype "bidirectional"))
      (node (ref "IC6") (pin "43") (pinfunction "GNDD4_43") (pintype "bidirectional"))
      (node (ref "IC6") (pin "45") (pinfunction "ADDR9_45") (pintype "bidirectional"))
      (node (ref "IC6") (pin "46") (pinfunction "ADDR8_46") (pintype "bidirectional"))
      (node (ref "IC6") (pin "47") (pinfunction "ADDR7_47") (pintype "bidirectional"))
      (node (ref "IC6") (pin "48") (pinfunction "ADDR6_48") (pintype "bidirectional"))
      (node (ref "IC6") (pin "49") (pinfunction "ADDR5_49") (pintype "bidirectional"))
      (node (ref "IC6") (pin "50") (pinfunction "ADDR4_50") (pintype "bidirectional"))
      (node (ref "IC6") (pin "51") (pinfunction "ADDR3_51") (pintype "bidirectional"))
      (node (ref "IC6") (pin "52") (pinfunction "ADDR2_52") (pintype "bidirectional"))
      (node (ref "IC6") (pin "53") (pinfunction "ADDR1_53") (pintype "bidirectional"))
      (node (ref "IC6") (pin "54") (pinfunction "ADDR0_54") (pintype "bidirectional"))
      (node (ref "IC6") (pin "63") (pinfunction "OPMODE0_63") (pintype "bidirectional"))
      (node (ref "IC6") (pin "64") (pinfunction "OPMODE1_64") (pintype "bidirectional"))
      (node (ref "IC6") (pin "65") (pinfunction "OPMODE2_65") (pintype "bidirectional"))
      (node (ref "IC6") (pin "68") (pinfunction "GNDD5_68") (pintype "bidirectional"))
      (node (ref "IC6") (pin "77") (pinfunction "GNDA2_77") (pintype "bidirectional"))
      (node (ref "IC7") (pin "2") (pinfunction "GND_2") (pintype "power_in"))
      (node (ref "IC7") (pin "4") (pinfunction "A1_4") (pintype "input"))
      (node (ref "IC7") (pin "5") (pinfunction "A0_5") (pintype "input"))
      (node (ref "J1") (pin "GND") (pinfunction "GND_GND") (pintype "bidirectional"))
      (node (ref "J1") (pin "GNDBREAK") (pinfunction "GNDBREAK_GNDBREAK") (pintype "bidirectional"))
      (node (ref "JP3") (pin "1") (pinfunction "GND[1]_1") (pintype "passive"))
      (node (ref "P2") (pin "6") (pinfunction "6_6") (pintype "passive"))
      (node (ref "P3") (pin "6") (pinfunction "6_6") (pintype "passive"))
      (node (ref "P4") (pin "6") (pinfunction "GND_6") (pintype "bidirectional"))
      (node (ref "P4") (pin "CD2") (pinfunction "CD2_CD2") (pintype "bidirectional"))
      (node (ref "P4") (pin "GND1") (pinfunction "SHIELD1_GND1") (pintype "bidirectional"))
      (node (ref "P4") (pin "GND2") (pinfunction "SHIELD2_GND2") (pintype "bidirectional"))
      (node (ref "Q2") (pin "2") (pinfunction "S_2") (pintype "passive"))
      (node (ref "Q3") (pin "2") (pinfunction "S_2") (pintype "passive"))
      (node (ref "R6") (pin "1") (pinfunction "1_1") (pintype "passive"))
      (node (ref "REG1") (pin "1") (pinfunction "ADJ_1") (pintype "input"))
      (node (ref "REG2") (pin "1") (pinfunction "GND_1") (pintype "input"))
      (node (ref "RN4") (pin "4") (pinfunction "1_4") (pintype "passive"))
      (node (ref "RN6") (pin "1") (pinfunction "1_1") (pintype "passive"))
      (node (ref "RN8") (pin "1") (pinfunction "1_1") (pintype "passive"))
      (node (ref "RN8") (pin "2") (pinfunction "1_2") (pintype "passive"))
      (node (ref "RN8") (pin "3") (pinfunction "1_3") (pintype "passive"))
      (node (ref "S1") (pin "1") (pinfunction "1_1") (pintype "passive"))
      (node (ref "S1") (pin "2") (pinfunction "2_2") (pintype "passive"))
      (node (ref "SJ1") (pin "2") (pinfunction "2_2") (pintype "passive"))
      (node (ref "SJ2") (pin "1") (pinfunction "1_1") (pintype "passive"))
      (node (ref "U1") (pin "GND1") (pinfunction "GND1_GND1") (pintype "bidirectional"))
      (node (ref "U1") (pin "GND2") (pinfunction "GND2_GND2") (pintype "bidirectional"))
    )
    (net (code "57") (name "Net-(C8-Pad2)") (class "Default")
      (node (ref "C8") (pin "2") (pinfunction "2_2") (pintype "passive"))
      (node (ref "R1") (pin "1") (pinfunction "1_1") (pintype "passive"))
      (node (ref "R2") (pin "2") (pinfunction "2_2") (pintype "passive"))
      (node (ref "X1") (pin "1") (pinfunction "1_1") (pintype "passive"))
    )
    (net (code "58") (name "Net-(C19-Pad1)") (class "Default")
      (node (ref "C19") (pin "1") (pinfunction "1_1") (pintype "passive"))
      (node (ref "SJ3") (pin "2") (pinfunction "2_2") (pintype "passive"))
    )
    (net (code "59") (name "Net-(CD-Pad1)") (class "Default")
      (node (ref "CD") (pin "1") (pinfunction "1_1") (pintype "passive"))
      (node (ref "P4") (pin "CD1") (pinfunction "CD1_CD1") (pintype "bidirectional"))
    )
    (net (code "60") (name "Net-(D1-PadA)") (class "Default")
      (node (ref "D1") (pin "A") (pinfunction "A_A") (pintype "passive"))
      (node (ref "J1") (pin "PWR") (pinfunction "PWR_PWR") (pintype "bidirectional"))
    )
    (net (code "61") (name "Net-(F1-Pad1)") (class "Default")
      (node (ref "F1") (pin "1") (pinfunction "1_1") (pintype "passive"))
      (node (ref "P1") (pin "VBUS") (pinfunction "VBUS_VBUS") (pintype "bidirectional"))
    )
    (net (code "62") (name "Net-(IC3-UCAP)") (class "Default")
      (node (ref "C11") (pin "1") (pinfunction "1_1") (pintype "passive"))
      (node (ref "IC3") (pin "27") (pinfunction "UCAP_27") (pintype "passive"))
    )
    (net (code "63") (name "Net-(IC3-XTAL1)") (class "Default")
      (node (ref "IC3") (pin "1") (pinfunction "XTAL1_1") (pintype "bidirectional"))
      (node (ref "R2") (pin "1") (pinfunction "1_1") (pintype "passive"))
    )
    (net (code "64") (name "Net-(IC3-XTAL2)") (class "Default")
      (node (ref "C2") (pin "2") (pinfunction "2_2") (pintype "passive"))
      (node (ref "IC3") (pin "2") (pinfunction "XTAL2_2") (pintype "bidirectional"))
      (node (ref "R1") (pin "2") (pinfunction "2_2") (pintype "passive"))
      (node (ref "X1") (pin "2") (pinfunction "2_2") (pintype "passive"))
    )
    (net (code "65") (name "Net-(IC4A-+IN)") (class "Default")
      (node (ref "IC4") (pin "3") (pinfunction "+IN_3") (pintype "input"))
      (node (ref "RN4") (pin "5") (pinfunction "2_5") (pintype "passive"))
      (node (ref "RN4") (pin "6") (pinfunction "2_6") (pintype "passive"))
    )
    (net (code "66") (name "Net-(IC4A-OUT)") (class "Default")
      (node (ref "IC4") (pin "1") (pinfunction "OUT_1") (pintype "output"))
      (node (ref "IC4") (pin "5") (pinfunction "+IN_5") (pintype "input"))
    )
    (net (code "67") (name "Net-(IC4B--IN)") (class "Default")
      (node (ref "IC4") (pin "6") (pinfunction "-IN_6") (pintype "input"))
      (node (ref "IC4") (pin "7") (pinfunction "OUT_7") (pintype "output"))
      (node (ref "Q1") (pin "1") (pinfunction "G_1") (pintype "passive"))
    )
    (net (code "68") (name "Net-(IC5-ADC6)") (class "Default")
      (node (ref "A6") (pin "1") (pinfunction "1_1") (pintype "passive"))
      (node (ref "IC5") (pin "19") (pinfunction "ADC6_19") (pintype "bidirectional"))
    )
    (net (code "69") (name "Net-(IC5-ADC7)") (class "Default")
      (node (ref "A7") (pin "1") (pinfunction "1_1") (pintype "passive"))
      (node (ref "IC5") (pin "22") (pinfunction "ADC7_22") (pintype "bidirectional"))
    )
    (net (code "70") (name "Net-(IC5-PB6(XTAL1{slash}TOSC1))") (class "Default")
      (node (ref "C20") (pin "2") (pinfunction "2_2") (pintype "passive"))
      (node (ref "IC5") (pin "7") (pinfunction "PB6(XTAL1/TOSC1)_7") (pintype "bidirectional"))
      (node (ref "R7") (pin "2") (pinfunction "2_2") (pintype "passive"))
      (node (ref "X3") (pin "2") (pinfunction "2_2") (pintype "passive"))
    )
    (net (code "71") (name "Net-(IC5-PB7(XTAL2{slash}TOSC2))") (class "Default")
      (node (ref "C21") (pin "2") (pinfunction "2_2") (pintype "passive"))
      (node (ref "IC5") (pin "8") (pinfunction "PB7(XTAL2/TOSC2)_8") (pintype "bidirectional"))
      (node (ref "R7") (pin "1") (pinfunction "1_1") (pintype "passive"))
      (node (ref "X3") (pin "1") (pinfunction "1_1") (pintype "passive"))
    )
    (net (code "72") (name "Net-(IC6-RSET_BG)") (class "Default")
      (node (ref "IC6") (pin "1") (pinfunction "RSET_BG_1") (pintype "bidirectional"))
      (node (ref "R6") (pin "2") (pinfunction "2_2") (pintype "passive"))
    )
    (net (code "73") (name "Net-(IC6-XTLN)") (class "Default")
      (node (ref "C16") (pin "1") (pinfunction "1_1") (pintype "passive"))
      (node (ref "IC6") (pin "75") (pinfunction "XTLN_75") (pintype "bidirectional"))
      (node (ref "R3") (pin "2") (pinfunction "2_2") (pintype "passive"))
      (node (ref "X2") (pin "2") (pinfunction "2_2") (pintype "passive"))
    )
    (net (code "74") (name "Net-(IC6-XTLP)") (class "Default")
      (node (ref "C15") (pin "1") (pinfunction "1_1") (pintype "passive"))
      (node (ref "IC6") (pin "76") (pinfunction "XTLP_76") (pintype "bidirectional"))
      (node (ref "R3") (pin "1") (pinfunction "1_1") (pintype "passive"))
      (node (ref "X2") (pin "1") (pinfunction "1_1") (pintype "passive"))
    )
    (net (code "75") (name "Net-(IC6-{slash}CS)") (class "Default")
      (node (ref "IC6") (pin "55") (pinfunction "/CS_55") (pintype "bidirectional"))
      (node (ref "IC6") (pin "57") (pinfunction "/WR_57") (pintype "bidirectional"))
      (node (ref "IC6") (pin "58") (pinfunction "/RD_58") (pintype "bidirectional"))
      (node (ref "RN7") (pin "2") (pinfunction "1_2") (pintype "passive"))
    )
    (net (code "76") (name "Net-(IC7-SCL)") (class "Default")
      (node (ref "IC7") (pin "1") (pinfunction "SCL_1") (pintype "bidirectional"))
      (node (ref "R15") (pin "2") (pinfunction "2_2") (pintype "passive"))
      (node (ref "SJ6") (pin "2") (pinfunction "2_2") (pintype "passive"))
    )
    (net (code "77") (name "Net-(IC7-SDA)") (class "Default")
      (node (ref "IC7") (pin "3") (pinfunction "SDA_3") (pintype "bidirectional"))
      (node (ref "R14") (pin "2") (pinfunction "2_2") (pintype "passive"))
      (node (ref "SJ5") (pin "2") (pinfunction "2_2") (pintype "passive"))
    )
    (net (code "78") (name "Net-(JP3-V+[3])") (class "Default")
      (node (ref "JP3") (pin "3") (pinfunction "V+[3]_3") (pintype "passive"))
      (node (ref "U1") (pin "P$9") (pinfunction "V+_P$9") (pintype "bidirectional"))
    )
    (net (code "79") (name "Net-(JP3-V-[2])") (class "Default")
      (node (ref "JP3") (pin "2") (pinfunction "V-[2]_2") (pintype "passive"))
      (node (ref "U1") (pin "P$10") (pinfunction "V-_P$10") (pintype "bidirectional"))
    )
    (net (code "80") (name "Net-(L3-Pad1)") (class "Default")
      (node (ref "L3") (pin "1") (pinfunction "1_1") (pintype "passive"))
      (node (ref "P1") (pin "FIX1") (pinfunction "FIX1_FIX1") (pintype "bidirectional"))
      (node (ref "P1") (pin "FIX2") (pinfunction "FIX2_FIX2") (pintype "bidirectional"))
      (node (ref "P1") (pin "PIN1") (pinfunction "PIN1_PIN1") (pintype "bidirectional"))
      (node (ref "P1") (pin "PIN2") (pinfunction "PIN2_PIN2") (pintype "bidirectional"))
      (node (ref "P1") (pin "TAB1") (pinfunction "TAB1_TAB1") (pintype "bidirectional"))
      (node (ref "P1") (pin "TAB2") (pinfunction "TAB2_TAB2") (pintype "bidirectional"))
      (node (ref "Z1") (pin "2") (pinfunction "2_2") (pintype "passive"))
      (node (ref "Z2") (pin "2") (pinfunction "2_2") (pintype "passive"))
    )
    (net (code "81") (name "Net-(LED5-PadC)") (class "Default")
      (node (ref "LED5") (pin "C") (pinfunction "C_C") (pintype "passive"))
      (node (ref "RN3") (pin "1") (pinfunction "1_1") (pintype "passive"))
    )
    (net (code "82") (name "Net-(LED10-PadC)") (class "Default")
      (node (ref "LED10") (pin "C") (pinfunction "C_C") (pintype "passive"))
      (node (ref "R8") (pin "2") (pinfunction "2_2") (pintype "passive"))
    )
    (net (code "83") (name "Net-(P1-PadD+)") (class "Default")
      (node (ref "P1") (pin "D+") (pinfunction "D+_D+") (pintype "bidirectional"))
      (node (ref "R5") (pin "2") (pinfunction "2_2") (pintype "passive"))
      (node (ref "Z1") (pin "1") (pinfunction "1_1") (pintype "passive"))
    )
    (net (code "84") (name "Net-(P1-PadD-)") (class "Default")
      (node (ref "P1") (pin "D-") (pinfunction "D-_D-") (pintype "bidirectional"))
      (node (ref "R4") (pin "2") (pinfunction "2_2") (pintype "passive"))
      (node (ref "Z2") (pin "1") (pinfunction "1_1") (pintype "passive"))
    )
    (net (code "85") (name "Net-(P4-CS)") (class "Default")
      (node (ref "P4") (pin "2") (pinfunction "CS_2") (pintype "bidirectional"))
      (node (ref "RN6") (pin "4") (pinfunction "1_4") (pintype "passive"))
      (node (ref "RN8") (pin "8") (pinfunction "2_8") (pintype "passive"))
    )
    (net (code "86") (name "Net-(P4-DI)") (class "Default")
      (node (ref "P4") (pin "3") (pinfunction "DI_3") (pintype "bidirectional"))
      (node (ref "RN6") (pin "3") (pinfunction "1_3") (pintype "passive"))
      (node (ref "RN8") (pin "6") (pinfunction "2_6") (pintype "passive"))
    )
    (net (code "87") (name "Net-(P4-SCK)") (class "Default")
      (node (ref "P4") (pin "5") (pinfunction "SCK_5") (pintype "bidirectional"))
      (node (ref "RN6") (pin "2") (pinfunction "1_2") (pintype "passive"))
      (node (ref "RN8") (pin "7") (pinfunction "2_7") (pintype "passive"))
    )
    (net (code "88") (name "Net-(Q2-D)") (class "Default")
      (node (ref "Q2") (pin "3") (pinfunction "D_3") (pintype "passive"))
      (node (ref "R8") (pin "1") (pinfunction "1_1") (pintype "passive"))
    )
    (net (code "89") (name "Net-(RN1A-2)") (class "Default")
      (node (ref "LED1") (pin "C") (pinfunction "C_C") (pintype "passive"))
      (node (ref "RN1") (pin "8") (pinfunction "2_8") (pintype "passive"))
    )
    (net (code "90") (name "Net-(RN1B-2)") (class "Default")
      (node (ref "LED3") (pin "C") (pinfunction "C_C") (pintype "passive"))
      (node (ref "RN1") (pin "7") (pinfunction "2_7") (pintype "passive"))
    )
    (net (code "91") (name "Net-(RN1C-2)") (class "Default")
      (node (ref "LED4") (pin "C") (pinfunction "C_C") (pintype "passive"))
      (node (ref "RN1") (pin "6") (pinfunction "2_6") (pintype "passive"))
    )
    (net (code "92") (name "Net-(RN1D-2)") (class "Default")
      (node (ref "LED7") (pin "C") (pinfunction "C_C") (pintype "passive"))
      (node (ref "RN1") (pin "5") (pinfunction "2_5") (pintype "passive"))
    )
    (net (code "93") (name "Net-(RN2B-1)") (class "Default")
      (node (ref "RN2") (pin "2") (pinfunction "1_2") (pintype "passive"))
      (node (ref "U1") (pin "P$12") (pinfunction "Y-_P$12") (pintype "bidirectional"))
    )
    (net (code "94") (name "Net-(RN2C-2)") (class "Default")
      (node (ref "LED8") (pin "C") (pinfunction "C_C") (pintype "passive"))
      (node (ref "RN2") (pin "6") (pinfunction "2_6") (pintype "passive"))
    )
    (net (code "95") (name "Net-(RN2D-2)") (class "Default")
      (node (ref "LED9") (pin "C") (pinfunction "C_C") (pintype "passive"))
      (node (ref "RN2") (pin "5") (pinfunction "2_5") (pintype "passive"))
    )
    (net (code "96") (name "Net-(RN3B-1)") (class "Default")
      (node (ref "LED6") (pin "C") (pinfunction "C_C") (pintype "passive"))
      (node (ref "RN3") (pin "2") (pinfunction "1_2") (pintype "passive"))
    )
    (net (code "97") (name "Net-(RN5A-2)") (class "Default")
      (node (ref "C23") (pin "1") (pinfunction "1_1") (pintype "passive"))
      (node (ref "RN5") (pin "7") (pinfunction "2_7") (pintype "passive"))
      (node (ref "RN5") (pin "8") (pinfunction "2_8") (pintype "passive"))
    )
    (net (code "98") (name "Net-(RN5C-2)") (class "Default")
      (node (ref "C24") (pin "1") (pinfunction "1_1") (pintype "passive"))
      (node (ref "RN5") (pin "5") (pinfunction "2_5") (pintype "passive"))
      (node (ref "RN5") (pin "6") (pinfunction "2_6") (pintype "passive"))
    )
    (net (code "99") (name "Net-(RN6A-2)") (class "Default")
      (node (ref "LED2") (pin "C") (pinfunction "C_C") (pintype "passive"))
      (node (ref "RN6") (pin "8") (pinfunction "2_8") (pintype "passive"))
    )
    (net (code "100") (name "Net-(U1-G-)") (class "Default")
      (node (ref "RN2") (pin "1") (pinfunction "1_1") (pintype "passive"))
      (node (ref "U1") (pin "P$14") (pinfunction "G-_P$14") (pintype "bidirectional"))
    )
    (net (code "101") (name "unconnected-(H2-Pad1)") (class "Default")
      (node (ref "H2") (pin "1") (pinfunction "1_1") (pintype "passive"))
    )
    (net (code "102") (name "unconnected-(H2-Pad2)") (class "Default")
      (node (ref "H2") (pin "2") (pinfunction "2_2") (pintype "passive"))
    )
    (net (code "103") (name "unconnected-(IC3-(RTS)PD6-Pad12)") (class "Default")
      (node (ref "IC3") (pin "12") (pinfunction "(RTS)PD6_12") (pintype "bidirectional"))
    )
    (net (code "104") (name "unconnected-(IC3-(SS)PB0-Pad14)") (class "Default")
      (node (ref "IC3") (pin "14") (pinfunction "(SS)PB0_14") (pintype "bidirectional"))
    )
    (net (code "105") (name "unconnected-(IC3-PB4-Pad18)") (class "Default")
      (node (ref "IC3") (pin "18") (pinfunction "PB4_18") (pintype "bidirectional"))
    )
    (net (code "106") (name "unconnected-(IC3-PB5-Pad19)") (class "Default")
      (node (ref "IC3") (pin "19") (pinfunction "PB5_19") (pintype "bidirectional"))
    )
    (net (code "107") (name "unconnected-(IC3-PB6-Pad20)") (class "Default")
      (node (ref "IC3") (pin "20") (pinfunction "PB6_20") (pintype "bidirectional"))
    )
    (net (code "108") (name "unconnected-(IC3-PB7-Pad21)") (class "Default")
      (node (ref "IC3") (pin "21") (pinfunction "PB7_21") (pintype "bidirectional"))
    )
    (net (code "109") (name "unconnected-(IC3-PC2-Pad5)") (class "Default")
      (node (ref "IC3") (pin "5") (pinfunction "PC2_5") (pintype "bidirectional"))
    )
    (net (code "110") (name "unconnected-(IC3-PC4-Pad26)") (class "Default")
      (node (ref "IC3") (pin "26") (pinfunction "PC4_26") (pintype "bidirectional"))
    )
    (net (code "111") (name "unconnected-(IC3-PC5-Pad25)") (class "Default")
      (node (ref "IC3") (pin "25") (pinfunction "PC5_25") (pintype "bidirectional"))
    )
    (net (code "112") (name "unconnected-(IC3-PC6-Pad23)") (class "Default")
      (node (ref "IC3") (pin "23") (pinfunction "PC6_23") (pintype "bidirectional"))
    )
    (net (code "113") (name "unconnected-(IC3-PC7-Pad22)") (class "Default")
      (node (ref "IC3") (pin "22") (pinfunction "PC7_22") (pintype "bidirectional"))
    )
    (net (code "114") (name "unconnected-(IC3-PD0-Pad6)") (class "Default")
      (node (ref "IC3") (pin "6") (pinfunction "PD0_6") (pintype "bidirectional"))
    )
    (net (code "115") (name "unconnected-(IC3-PD1-Pad7)") (class "Default")
      (node (ref "IC3") (pin "7") (pinfunction "PD1_7") (pintype "bidirectional"))
    )
    (net (code "116") (name "unconnected-(IC6-NC0-Pad3)") (class "Default")
      (node (ref "IC6") (pin "3") (pinfunction "NC0_3") (pintype "bidirectional"))
    )
    (net (code "117") (name "unconnected-(IC6-NC1-Pad60)") (class "Default")
      (node (ref "IC6") (pin "60") (pinfunction "NC1_60") (pintype "bidirectional"))
    )
    (net (code "118") (name "unconnected-(IC6-NC2-Pad61)") (class "Default")
      (node (ref "IC6") (pin "61") (pinfunction "NC2_61") (pintype "bidirectional"))
    )
    (net (code "119") (name "unconnected-(IC6-NC3-Pad62)") (class "Default")
      (node (ref "IC6") (pin "62") (pinfunction "NC3_62") (pintype "bidirectional"))
    )
    (net (code "120") (name "unconnected-(IC6-NC4-Pad78)") (class "Default")
      (node (ref "IC6") (pin "78") (pinfunction "NC4_78") (pintype "bidirectional"))
    )
    (net (code "121") (name "unconnected-(IC6-NC5-Pad79)") (class "Default")
      (node (ref "IC6") (pin "79") (pinfunction "NC5_79") (pintype "bidirectional"))
    )
    (net (code "122") (name "unconnected-(IC6-NC6-Pad80)") (class "Default")
      (node (ref "IC6") (pin "80") (pinfunction "NC6_80") (pintype "bidirectional"))
    )
    (net (code "123") (name "unconnected-(JP3-PadMNT1)") (class "Default")
      (node (ref "JP3") (pin "MNT1") (pinfunction "MNT1_MNT1") (pintype "passive"))
    )
    (net (code "124") (name "unconnected-(JP3-PadMNT2)") (class "Default")
      (node (ref "JP3") (pin "MNT2") (pinfunction "MNT2_MNT2") (pintype "passive"))
    )
    (net (code "125") (name "unconnected-(P1-PadID)") (class "Default")
      (node (ref "P1") (pin "ID") (pinfunction "ID_ID") (pintype "bidirectional"))
    )
    (net (code "126") (name "unconnected-(P4-NC-Pad1)") (class "Default")
      (node (ref "P4") (pin "1") (pinfunction "NC_1") (pintype "bidirectional"))
    )
    (net (code "127") (name "unconnected-(P4-RSV-Pad8)") (class "Default")
      (node (ref "P4") (pin "8") (pinfunction "RSV_8") (pintype "bidirectional"))
    )
    (net (code "128") (name "unconnected-(RN7-Pad1)") (class "Default")
      (node (ref "RN7") (pin "1") (pinfunction "1_1") (pintype "passive"))
    )
    (net (code "129") (name "unconnected-(RN7A-2-Pad8)") (class "Default")
      (node (ref "RN7") (pin "8") (pinfunction "2_8") (pintype "passive"))
    )
    (net (code "130") (name "unconnected-(RN7C-1-Pad3)") (class "Default")
      (node (ref "RN7") (pin "3") (pinfunction "1_3") (pintype "passive"))
    )
    (net (code "131") (name "unconnected-(RN7C-2-Pad6)") (class "Default")
      (node (ref "RN7") (pin "6") (pinfunction "2_6") (pintype "passive"))
    )
    (net (code "132") (name "unconnected-(RN8D-1-Pad4)") (class "Default")
      (node (ref "RN8") (pin "4") (pinfunction "1_4") (pintype "passive"))
    )
    (net (code "133") (name "unconnected-(RN8D-2-Pad5)") (class "Default")
      (node (ref "RN8") (pin "5") (pinfunction "2_5") (pintype "passive"))
    )
  )
)
